# DIGREG1.net
KiCad netlist of a schematic drawn in EAGLE
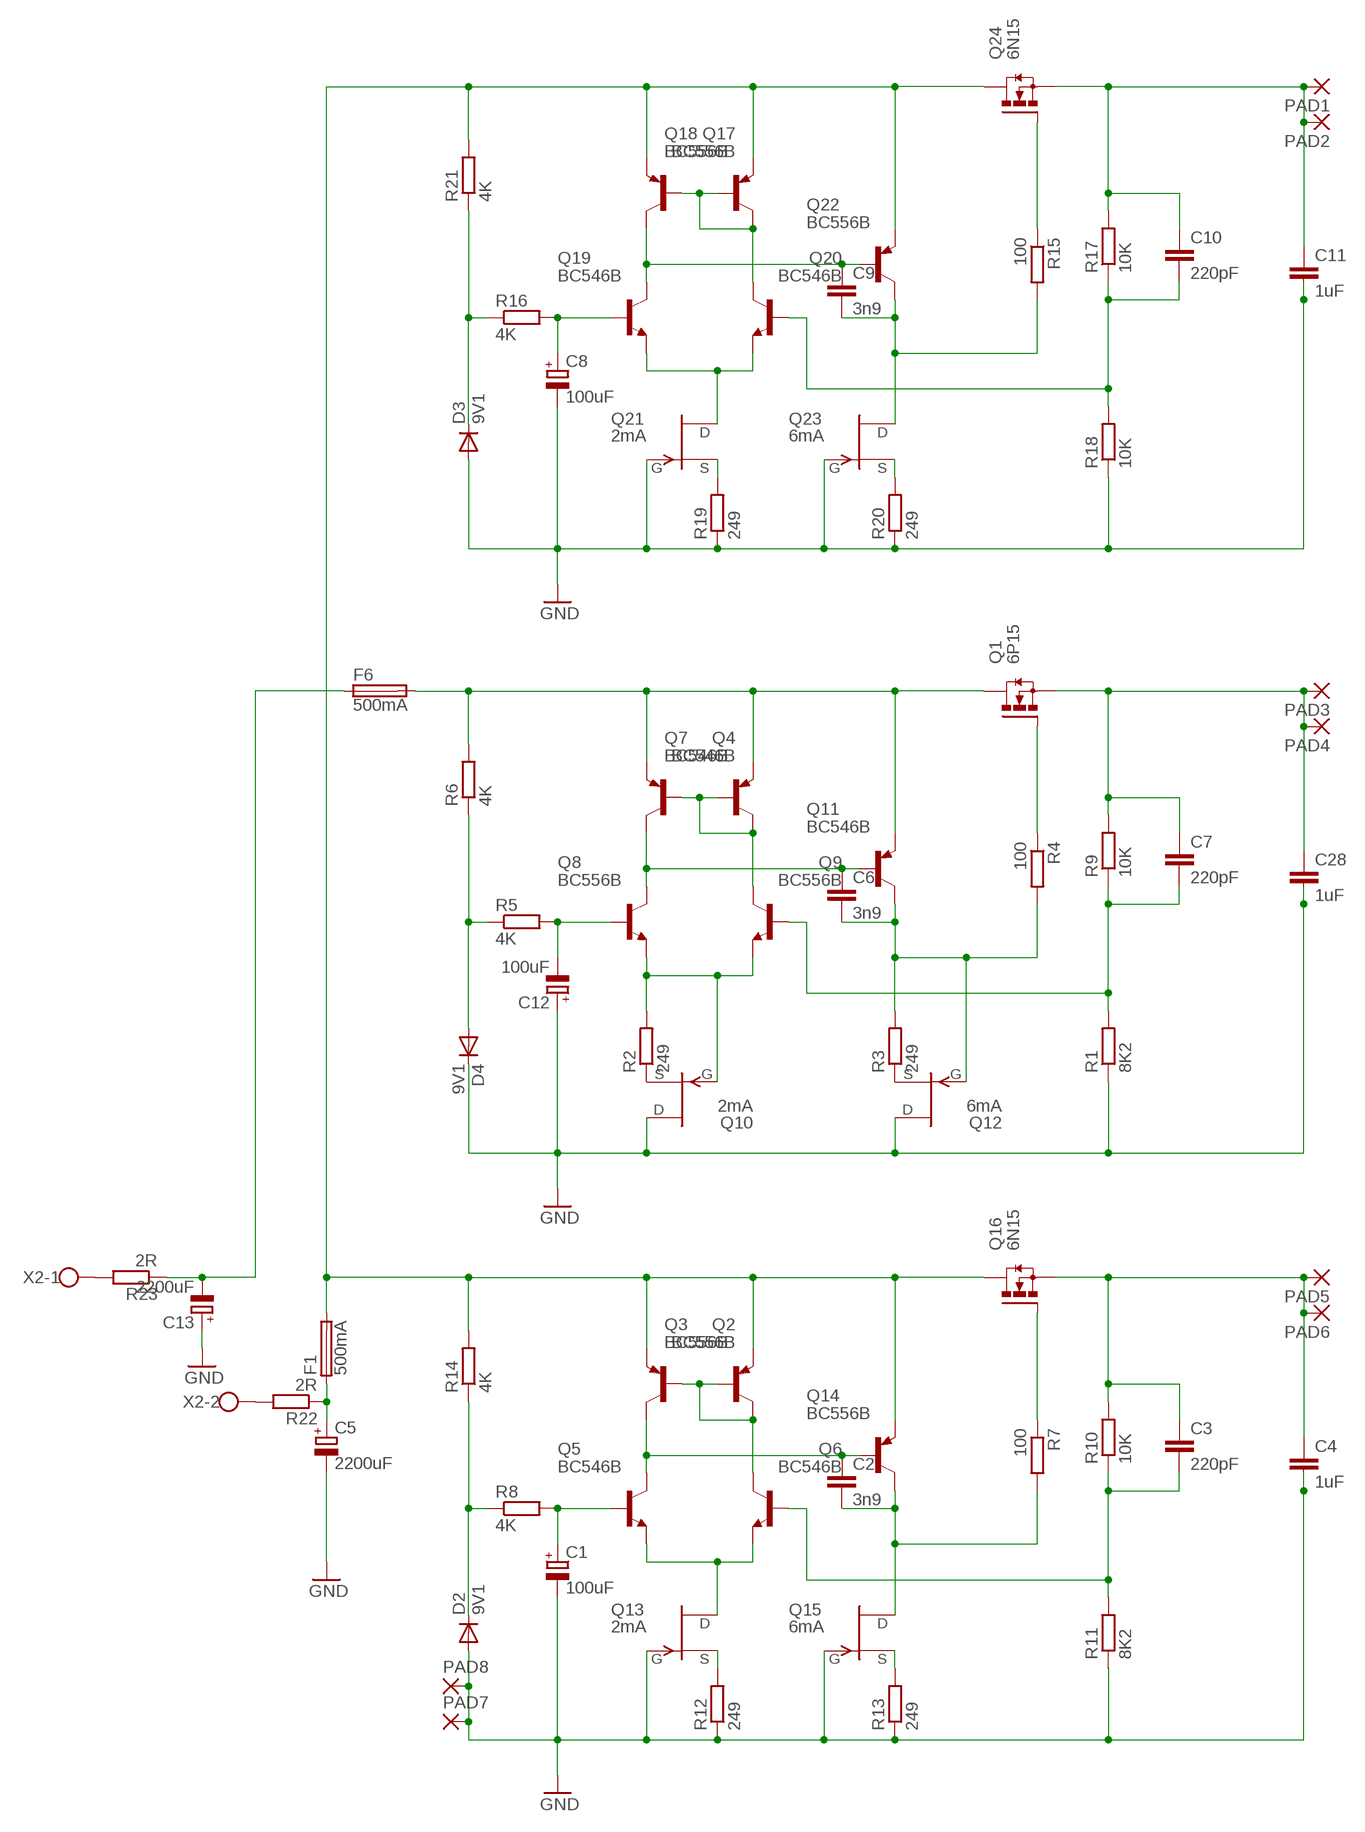
[diagram p0: schematic, sheet 1]

(export (version "E")
  (design (tool "Eeschema 10.0.6"))
  (components
    (comp (ref "C1")
      (value "100uF")
      (footprint "eagle-import:E3,5-8")
      (libsource (lib "eagle-import") (part "CPOL-EUE3.5-8"))
    )
    (comp (ref "C2")
      (value "3n9")
      (footprint "eagle-import:C1210K")
      (libsource (lib "eagle-import") (part "C-EUC1210K"))
    )
    (comp (ref "C3")
      (value "220pF")
      (footprint "eagle-import:C1210")
      (libsource (lib "eagle-import") (part "C-EUC1210"))
    )
    (comp (ref "C4")
      (value "1uF")
      (footprint "eagle-import:C275-134X316")
      (libsource (lib "eagle-import") (part "C-EU275-134X316"))
    )
    (comp (ref "C5")
      (value "2200uF")
      (footprint "eagle-import:E7,5-18")
      (libsource (lib "eagle-import") (part "CPOL-EUE7.5-18"))
    )
    (comp (ref "C6")
      (value "3n9")
      (footprint "eagle-import:C1210K")
      (libsource (lib "eagle-import") (part "C-EUC1210K"))
    )
    (comp (ref "C7")
      (value "220pF")
      (footprint "eagle-import:C1210")
      (libsource (lib "eagle-import") (part "C-EUC1210"))
    )
    (comp (ref "C8")
      (value "100uF")
      (footprint "eagle-import:E3,5-8")
      (libsource (lib "eagle-import") (part "CPOL-EUE3.5-8"))
    )
    (comp (ref "C9")
      (value "3n9")
      (footprint "eagle-import:C1210K")
      (libsource (lib "eagle-import") (part "C-EUC1210K"))
    )
    (comp (ref "C10")
      (value "220pF")
      (footprint "eagle-import:C1210")
      (libsource (lib "eagle-import") (part "C-EUC1210"))
    )
    (comp (ref "C11")
      (value "1uF")
      (footprint "eagle-import:C275-134X316")
      (libsource (lib "eagle-import") (part "C-EU275-134X316"))
    )
    (comp (ref "C12")
      (value "100uF")
      (footprint "eagle-import:E3,5-8")
      (libsource (lib "eagle-import") (part "CPOL-EUE3.5-8"))
    )
    (comp (ref "C13")
      (value "2200uF")
      (footprint "eagle-import:E7,5-18")
      (libsource (lib "eagle-import") (part "CPOL-EUE7.5-18"))
    )
    (comp (ref "C28")
      (value "1uF")
      (footprint "eagle-import:C275-134X316")
      (libsource (lib "eagle-import") (part "C-EU275-134X316"))
    )
    (comp (ref "D2")
      (value "9V1")
      (footprint "eagle-import:DO35-7")
      (libsource (lib "eagle-import") (part "1N4148DO35-7"))
    )
    (comp (ref "D3")
      (value "9V1")
      (footprint "eagle-import:DO35-7")
      (libsource (lib "eagle-import") (part "1N4148DO35-7"))
    )
    (comp (ref "D4")
      (value "9V1")
      (footprint "eagle-import:DO35-7")
      (libsource (lib "eagle-import") (part "1N4148DO35-7"))
    )
    (comp (ref "F1")
      (value "500mA")
      (footprint "eagle-import:19560")
      (libsource (lib "eagle-import") (part "19560"))
    )
    (comp (ref "F6")
      (value "500mA")
      (footprint "eagle-import:19560")
      (libsource (lib "eagle-import") (part "19560"))
    )
    (comp (ref "PAD1")
      (value "3,81/1,4")
      (footprint "eagle-import:3,81_1,4")
      (libsource (lib "eagle-import") (part "3,81/1,4"))
    )
    (comp (ref "PAD2")
      (value "3,81/1,4")
      (footprint "eagle-import:3,81_1,4")
      (libsource (lib "eagle-import") (part "3,81/1,4"))
    )
    (comp (ref "PAD3")
      (value "3,81/1,4")
      (footprint "eagle-import:3,81_1,4")
      (libsource (lib "eagle-import") (part "3,81/1,4"))
    )
    (comp (ref "PAD4")
      (value "3,81/1,4")
      (footprint "eagle-import:3,81_1,4")
      (libsource (lib "eagle-import") (part "3,81/1,4"))
    )
    (comp (ref "PAD5")
      (value "3,81/1,4")
      (footprint "eagle-import:3,81_1,4")
      (libsource (lib "eagle-import") (part "3,81/1,4"))
    )
    (comp (ref "PAD6")
      (value "3,81/1,4")
      (footprint "eagle-import:3,81_1,4")
      (libsource (lib "eagle-import") (part "3,81/1,4"))
    )
    (comp (ref "PAD7")
      (value "3,81/1,4")
      (footprint "eagle-import:3,81_1,4")
      (libsource (lib "eagle-import") (part "3,81/1,4"))
    )
    (comp (ref "PAD8")
      (value "3,81/1,4")
      (footprint "eagle-import:3,81_1,4")
      (libsource (lib "eagle-import") (part "3,81/1,4"))
    )
    (comp (ref "Q1")
      (value "6P15")
      (footprint "eagle-import:TO220BH")
      (libsource (lib "eagle-import") (part "IRFI540NPBF"))
    )
    (comp (ref "Q2")
      (value "BC556B")
      (footprint "eagle-import:TO92-EBC")
      (libsource (lib "eagle-import") (part "BC560"))
    )
    (comp (ref "Q3")
      (value "BC556B")
      (footprint "eagle-import:TO92-EBC")
      (libsource (lib "eagle-import") (part "BC560"))
    )
    (comp (ref "Q4")
      (value "BC546B")
      (footprint "eagle-import:TO92-EBC")
      (libsource (lib "eagle-import") (part "BC560"))
    )
    (comp (ref "Q5")
      (value "BC546B")
      (footprint "eagle-import:TO92-EBC")
      (libsource (lib "eagle-import") (part "BC550B"))
    )
    (comp (ref "Q6")
      (value "BC546B")
      (footprint "eagle-import:TO92-EBC")
      (libsource (lib "eagle-import") (part "BC550B"))
    )
    (comp (ref "Q7")
      (value "BC546B")
      (footprint "eagle-import:TO92-EBC")
      (libsource (lib "eagle-import") (part "BC560"))
    )
    (comp (ref "Q8")
      (value "BC556B")
      (footprint "eagle-import:TO92-EBC")
      (libsource (lib "eagle-import") (part "BC550B"))
    )
    (comp (ref "Q9")
      (value "BC556B")
      (footprint "eagle-import:TO92-EBC")
      (libsource (lib "eagle-import") (part "BC550B"))
    )
    (comp (ref "Q10")
      (value "2mA")
      (footprint "eagle-import:TO92-")
      (libsource (lib "eagle-import") (part "?5482N4"))
    )
    (comp (ref "Q11")
      (value "BC546B")
      (footprint "eagle-import:TO92-EBC")
      (libsource (lib "eagle-import") (part "BC560"))
    )
    (comp (ref "Q12")
      (value "6mA")
      (footprint "eagle-import:TO92-")
      (libsource (lib "eagle-import") (part "?5482N4"))
    )
    (comp (ref "Q13")
      (value "2mA")
      (footprint "eagle-import:TO92-")
      (libsource (lib "eagle-import") (part "?5482N4"))
    )
    (comp (ref "Q14")
      (value "BC556B")
      (footprint "eagle-import:TO92-EBC")
      (libsource (lib "eagle-import") (part "BC560"))
    )
    (comp (ref "Q15")
      (value "6mA")
      (footprint "eagle-import:TO92-")
      (libsource (lib "eagle-import") (part "?5482N4"))
    )
    (comp (ref "Q16")
      (value "6N15")
      (footprint "eagle-import:TO220BH")
      (libsource (lib "eagle-import") (part "IRFI540NPBF"))
    )
    (comp (ref "Q17")
      (value "BC556B")
      (footprint "eagle-import:TO92-EBC")
      (libsource (lib "eagle-import") (part "BC560"))
    )
    (comp (ref "Q18")
      (value "BC556B")
      (footprint "eagle-import:TO92-EBC")
      (libsource (lib "eagle-import") (part "BC560"))
    )
    (comp (ref "Q19")
      (value "BC546B")
      (footprint "eagle-import:TO92-EBC")
      (libsource (lib "eagle-import") (part "BC550B"))
    )
    (comp (ref "Q20")
      (value "BC546B")
      (footprint "eagle-import:TO92-EBC")
      (libsource (lib "eagle-import") (part "BC550B"))
    )
    (comp (ref "Q21")
      (value "2mA")
      (footprint "eagle-import:TO92-")
      (libsource (lib "eagle-import") (part "?5482N4"))
    )
    (comp (ref "Q22")
      (value "BC556B")
      (footprint "eagle-import:TO92-EBC")
      (libsource (lib "eagle-import") (part "BC560"))
    )
    (comp (ref "Q23")
      (value "6mA")
      (footprint "eagle-import:TO92-")
      (libsource (lib "eagle-import") (part "?5482N4"))
    )
    (comp (ref "Q24")
      (value "6N15")
      (footprint "eagle-import:TO220BH")
      (libsource (lib "eagle-import") (part "IRFI540NPBF"))
    )
    (comp (ref "R1")
      (value "8K2")
      (footprint "eagle-import:R1210")
      (libsource (lib "eagle-import") (part "R-EU_R1210"))
    )
    (comp (ref "R2")
      (value "249")
      (footprint "eagle-import:R1210")
      (libsource (lib "eagle-import") (part "R-EU_R1210"))
    )
    (comp (ref "R3")
      (value "249")
      (footprint "eagle-import:R1210")
      (libsource (lib "eagle-import") (part "R-EU_R1210"))
    )
    (comp (ref "R4")
      (value "100")
      (footprint "eagle-import:0309_12")
      (libsource (lib "eagle-import") (part "R-EU_0309/12"))
    )
    (comp (ref "R5")
      (value "4K")
      (footprint "eagle-import:0309_12")
      (libsource (lib "eagle-import") (part "R-EU_0309/12"))
    )
    (comp (ref "R6")
      (value "4K")
      (footprint "eagle-import:0309_12")
      (libsource (lib "eagle-import") (part "R-EU_0309/12"))
    )
    (comp (ref "R7")
      (value "100")
      (footprint "eagle-import:0309_12")
      (libsource (lib "eagle-import") (part "R-EU_0309/12"))
    )
    (comp (ref "R8")
      (value "4K")
      (footprint "eagle-import:0309_12")
      (libsource (lib "eagle-import") (part "R-EU_0309/12"))
    )
    (comp (ref "R9")
      (value "10K")
      (footprint "eagle-import:R1210")
      (libsource (lib "eagle-import") (part "R-EU_R1210"))
    )
    (comp (ref "R10")
      (value "10K")
      (footprint "eagle-import:R1210")
      (libsource (lib "eagle-import") (part "R-EU_R1210"))
    )
    (comp (ref "R11")
      (value "8K2")
      (footprint "eagle-import:R1210")
      (libsource (lib "eagle-import") (part "R-EU_R1210"))
    )
    (comp (ref "R12")
      (value "249")
      (footprint "eagle-import:R1210")
      (libsource (lib "eagle-import") (part "R-EU_R1210"))
    )
    (comp (ref "R13")
      (value "249")
      (footprint "eagle-import:R1210")
      (libsource (lib "eagle-import") (part "R-EU_R1210"))
    )
    (comp (ref "R14")
      (value "4K")
      (footprint "eagle-import:0309_12")
      (libsource (lib "eagle-import") (part "R-EU_0309/12"))
    )
    (comp (ref "R15")
      (value "100")
      (footprint "eagle-import:0309_12")
      (libsource (lib "eagle-import") (part "R-EU_0309/12"))
    )
    (comp (ref "R16")
      (value "4K")
      (footprint "eagle-import:0309_12")
      (libsource (lib "eagle-import") (part "R-EU_0309/12"))
    )
    (comp (ref "R17")
      (value "10K")
      (footprint "eagle-import:R1210")
      (libsource (lib "eagle-import") (part "R-EU_R1210"))
    )
    (comp (ref "R18")
      (value "10K")
      (footprint "eagle-import:R1210")
      (libsource (lib "eagle-import") (part "R-EU_R1210"))
    )
    (comp (ref "R19")
      (value "249")
      (footprint "eagle-import:R1210")
      (libsource (lib "eagle-import") (part "R-EU_R1210"))
    )
    (comp (ref "R20")
      (value "249")
      (footprint "eagle-import:R1210")
      (libsource (lib "eagle-import") (part "R-EU_R1210"))
    )
    (comp (ref "R21")
      (value "4K")
      (footprint "eagle-import:0309_12")
      (libsource (lib "eagle-import") (part "R-EU_0309/12"))
    )
    (comp (ref "R22")
      (value "2R")
      (footprint "eagle-import:0309_12")
      (libsource (lib "eagle-import") (part "R-EU_0309/12"))
    )
    (comp (ref "R23")
      (value "2R")
      (footprint "eagle-import:0309_12")
      (libsource (lib "eagle-import") (part "R-EU_0309/12"))
    )
    (comp (ref "X2")
      (value "W237-102")
      (footprint "eagle-import:W237-102")
      (fields
        (field (name "MPN") "237-102")
        (field (name "MPN_1") "237-102")
        (field (name "OC_FARNELL") "unknown")
        (field (name "OC_NEWARK") "70K9898")
      )
      (libsource (lib "eagle-import") (part "W237-102"))
    )
  )
  (nets
    (net (code "1") (name "GND") (class "Default")
      (node (ref "C1") (pin "-") (pinfunction "-_-") (pintype "passive"))
      (node (ref "C11") (pin "2") (pinfunction "2_2") (pintype "passive"))
      (node (ref "C12") (pin "+") (pinfunction "+_+") (pintype "passive"))
      (node (ref "C13") (pin "+") (pinfunction "+_+") (pintype "passive"))
      (node (ref "C28") (pin "2") (pinfunction "2_2") (pintype "passive"))
      (node (ref "C4") (pin "2") (pinfunction "2_2") (pintype "passive"))
      (node (ref "C5") (pin "-") (pinfunction "-_-") (pintype "passive"))
      (node (ref "C8") (pin "-") (pinfunction "-_-") (pintype "passive"))
      (node (ref "D2") (pin "A") (pinfunction "A_A") (pintype "passive"))
      (node (ref "D3") (pin "A") (pinfunction "A_A") (pintype "passive"))
      (node (ref "D4") (pin "C") (pinfunction "C_C") (pintype "passive"))
      (node (ref "PAD7") (pin "1") (pinfunction "P_1") (pintype "passive"))
      (node (ref "PAD8") (pin "1") (pinfunction "P_1") (pintype "passive"))
      (node (ref "Q10") (pin "3") (pinfunction "D_3") (pintype "passive"))
      (node (ref "Q12") (pin "3") (pinfunction "D_3") (pintype "passive"))
      (node (ref "Q13") (pin "1") (pinfunction "G_1") (pintype "passive"))
      (node (ref "Q15") (pin "1") (pinfunction "G_1") (pintype "passive"))
      (node (ref "Q21") (pin "1") (pinfunction "G_1") (pintype "passive"))
      (node (ref "Q23") (pin "1") (pinfunction "G_1") (pintype "passive"))
      (node (ref "R1") (pin "1") (pinfunction "1_1") (pintype "passive"))
      (node (ref "R11") (pin "1") (pinfunction "1_1") (pintype "passive"))
      (node (ref "R12") (pin "1") (pinfunction "1_1") (pintype "passive"))
      (node (ref "R13") (pin "1") (pinfunction "1_1") (pintype "passive"))
      (node (ref "R18") (pin "1") (pinfunction "1_1") (pintype "passive"))
      (node (ref "R19") (pin "1") (pinfunction "1_1") (pintype "passive"))
      (node (ref "R20") (pin "1") (pinfunction "1_1") (pintype "passive"))
    )
    (net (code "2") (name "Net-(C1-Pad+)") (class "Default")
      (node (ref "C1") (pin "+") (pinfunction "+_+") (pintype "passive"))
      (node (ref "Q5") (pin "B") (pinfunction "B_B") (pintype "passive"))
      (node (ref "R8") (pin "2") (pinfunction "2_2") (pintype "passive"))
    )
    (net (code "3") (name "Net-(C2-Pad1)") (class "Default")
      (node (ref "C2") (pin "1") (pinfunction "1_1") (pintype "passive"))
      (node (ref "Q14") (pin "B") (pinfunction "B_B") (pintype "passive"))
      (node (ref "Q2") (pin "C") (pinfunction "C_C") (pintype "passive"))
      (node (ref "Q5") (pin "C") (pinfunction "C_C") (pintype "passive"))
    )
    (net (code "4") (name "Net-(C3-Pad2)") (class "Default")
      (node (ref "C3") (pin "2") (pinfunction "2_2") (pintype "passive"))
      (node (ref "Q6") (pin "B") (pinfunction "B_B") (pintype "passive"))
      (node (ref "R10") (pin "1") (pinfunction "1_1") (pintype "passive"))
      (node (ref "R11") (pin "2") (pinfunction "2_2") (pintype "passive"))
    )
    (net (code "5") (name "Net-(C5-Pad+)") (class "Default")
      (node (ref "C5") (pin "+") (pinfunction "+_+") (pintype "passive"))
      (node (ref "F1") (pin "1") (pinfunction "1_1") (pintype "passive"))
      (node (ref "R22") (pin "1") (pinfunction "1_1") (pintype "passive"))
    )
    (net (code "6") (name "Net-(C6-Pad1)") (class "Default")
      (node (ref "C6") (pin "1") (pinfunction "1_1") (pintype "passive"))
      (node (ref "Q11") (pin "B") (pinfunction "B_B") (pintype "passive"))
      (node (ref "Q4") (pin "C") (pinfunction "C_C") (pintype "passive"))
      (node (ref "Q8") (pin "C") (pinfunction "C_C") (pintype "passive"))
    )
    (net (code "7") (name "Net-(C7-Pad2)") (class "Default")
      (node (ref "C7") (pin "2") (pinfunction "2_2") (pintype "passive"))
      (node (ref "Q9") (pin "B") (pinfunction "B_B") (pintype "passive"))
      (node (ref "R1") (pin "2") (pinfunction "2_2") (pintype "passive"))
      (node (ref "R9") (pin "1") (pinfunction "1_1") (pintype "passive"))
    )
    (net (code "8") (name "Net-(C8-Pad+)") (class "Default")
      (node (ref "C8") (pin "+") (pinfunction "+_+") (pintype "passive"))
      (node (ref "Q19") (pin "B") (pinfunction "B_B") (pintype "passive"))
      (node (ref "R16") (pin "2") (pinfunction "2_2") (pintype "passive"))
    )
    (net (code "9") (name "Net-(C9-Pad1)") (class "Default")
      (node (ref "C9") (pin "1") (pinfunction "1_1") (pintype "passive"))
      (node (ref "Q17") (pin "C") (pinfunction "C_C") (pintype "passive"))
      (node (ref "Q19") (pin "C") (pinfunction "C_C") (pintype "passive"))
      (node (ref "Q22") (pin "B") (pinfunction "B_B") (pintype "passive"))
    )
    (net (code "10") (name "Net-(C10-Pad2)") (class "Default")
      (node (ref "C10") (pin "2") (pinfunction "2_2") (pintype "passive"))
      (node (ref "Q20") (pin "B") (pinfunction "B_B") (pintype "passive"))
      (node (ref "R17") (pin "1") (pinfunction "1_1") (pintype "passive"))
      (node (ref "R18") (pin "2") (pinfunction "2_2") (pintype "passive"))
    )
    (net (code "11") (name "Net-(C12-Pad-)") (class "Default")
      (node (ref "C12") (pin "-") (pinfunction "-_-") (pintype "passive"))
      (node (ref "Q8") (pin "B") (pinfunction "B_B") (pintype "passive"))
      (node (ref "R5") (pin "2") (pinfunction "2_2") (pintype "passive"))
    )
    (net (code "12") (name "Net-(C13-Pad-)") (class "Default")
      (node (ref "C13") (pin "-") (pinfunction "-_-") (pintype "passive"))
      (node (ref "F6") (pin "1") (pinfunction "1_1") (pintype "passive"))
      (node (ref "R23") (pin "1") (pinfunction "1_1") (pintype "passive"))
    )
    (net (code "13") (name "Net-(D2-PadC)") (class "Default")
      (node (ref "D2") (pin "C") (pinfunction "C_C") (pintype "passive"))
      (node (ref "R14") (pin "1") (pinfunction "1_1") (pintype "passive"))
      (node (ref "R8") (pin "1") (pinfunction "1_1") (pintype "passive"))
    )
    (net (code "14") (name "Net-(D3-PadC)") (class "Default")
      (node (ref "D3") (pin "C") (pinfunction "C_C") (pintype "passive"))
      (node (ref "R16") (pin "1") (pinfunction "1_1") (pintype "passive"))
      (node (ref "R21") (pin "1") (pinfunction "1_1") (pintype "passive"))
    )
    (net (code "15") (name "Net-(D4-PadA)") (class "Default")
      (node (ref "D4") (pin "A") (pinfunction "A_A") (pintype "passive"))
      (node (ref "R5") (pin "1") (pinfunction "1_1") (pintype "passive"))
      (node (ref "R6") (pin "1") (pinfunction "1_1") (pintype "passive"))
    )
    (net (code "16") (name "Net-(F1-Pad2)") (class "Default")
      (node (ref "F1") (pin "2") (pinfunction "2_2") (pintype "passive"))
      (node (ref "Q14") (pin "E") (pinfunction "E_E") (pintype "passive"))
      (node (ref "Q16") (pin "D") (pinfunction "D_D") (pintype "passive"))
      (node (ref "Q17") (pin "E") (pinfunction "E_E") (pintype "passive"))
      (node (ref "Q18") (pin "E") (pinfunction "E_E") (pintype "passive"))
      (node (ref "Q2") (pin "E") (pinfunction "E_E") (pintype "passive"))
      (node (ref "Q22") (pin "E") (pinfunction "E_E") (pintype "passive"))
      (node (ref "Q24") (pin "D") (pinfunction "D_D") (pintype "passive"))
      (node (ref "Q3") (pin "E") (pinfunction "E_E") (pintype "passive"))
      (node (ref "R14") (pin "2") (pinfunction "2_2") (pintype "passive"))
      (node (ref "R21") (pin "2") (pinfunction "2_2") (pintype "passive"))
    )
    (net (code "17") (name "Net-(F6-Pad2)") (class "Default")
      (node (ref "F6") (pin "2") (pinfunction "2_2") (pintype "passive"))
      (node (ref "Q1") (pin "D") (pinfunction "D_D") (pintype "passive"))
      (node (ref "Q11") (pin "E") (pinfunction "E_E") (pintype "passive"))
      (node (ref "Q4") (pin "E") (pinfunction "E_E") (pintype "passive"))
      (node (ref "Q7") (pin "E") (pinfunction "E_E") (pintype "passive"))
      (node (ref "R6") (pin "2") (pinfunction "2_2") (pintype "passive"))
    )
    (net (code "18") (name "Net-(PAD1-P)") (class "Default")
      (node (ref "C10") (pin "1") (pinfunction "1_1") (pintype "passive"))
      (node (ref "C11") (pin "1") (pinfunction "1_1") (pintype "passive"))
      (node (ref "PAD1") (pin "1") (pinfunction "P_1") (pintype "passive"))
      (node (ref "PAD2") (pin "1") (pinfunction "P_1") (pintype "passive"))
      (node (ref "Q24") (pin "S") (pinfunction "S_S") (pintype "passive"))
      (node (ref "R17") (pin "2") (pinfunction "2_2") (pintype "passive"))
    )
    (net (code "19") (name "Net-(PAD3-P)") (class "Default")
      (node (ref "C28") (pin "1") (pinfunction "1_1") (pintype "passive"))
      (node (ref "C7") (pin "1") (pinfunction "1_1") (pintype "passive"))
      (node (ref "PAD3") (pin "1") (pinfunction "P_1") (pintype "passive"))
      (node (ref "PAD4") (pin "1") (pinfunction "P_1") (pintype "passive"))
      (node (ref "Q1") (pin "S") (pinfunction "S_S") (pintype "passive"))
      (node (ref "R9") (pin "2") (pinfunction "2_2") (pintype "passive"))
    )
    (net (code "20") (name "Net-(PAD5-P)") (class "Default")
      (node (ref "C3") (pin "1") (pinfunction "1_1") (pintype "passive"))
      (node (ref "C4") (pin "1") (pinfunction "1_1") (pintype "passive"))
      (node (ref "PAD5") (pin "1") (pinfunction "P_1") (pintype "passive"))
      (node (ref "PAD6") (pin "1") (pinfunction "P_1") (pintype "passive"))
      (node (ref "Q16") (pin "S") (pinfunction "S_S") (pintype "passive"))
      (node (ref "R10") (pin "2") (pinfunction "2_2") (pintype "passive"))
    )
    (net (code "21") (name "Net-(Q1-PadG)") (class "Default")
      (node (ref "Q1") (pin "G") (pinfunction "G_G") (pintype "passive"))
      (node (ref "R4") (pin "1") (pinfunction "1_1") (pintype "passive"))
    )
    (net (code "22") (name "Net-(Q2-PadB)") (class "Default")
      (node (ref "Q2") (pin "B") (pinfunction "B_B") (pintype "passive"))
      (node (ref "Q3") (pin "B") (pinfunction "B_B") (pintype "passive"))
      (node (ref "Q3") (pin "C") (pinfunction "C_C") (pintype "passive"))
      (node (ref "Q6") (pin "C") (pinfunction "C_C") (pintype "passive"))
    )
    (net (code "23") (name "Net-(Q4-PadB)") (class "Default")
      (node (ref "Q4") (pin "B") (pinfunction "B_B") (pintype "passive"))
      (node (ref "Q7") (pin "B") (pinfunction "B_B") (pintype "passive"))
      (node (ref "Q7") (pin "C") (pinfunction "C_C") (pintype "passive"))
      (node (ref "Q9") (pin "C") (pinfunction "C_C") (pintype "passive"))
    )
    (net (code "24") (name "Net-(Q10-G)") (class "Default")
      (node (ref "Q10") (pin "1") (pinfunction "G_1") (pintype "passive"))
      (node (ref "Q8") (pin "E") (pinfunction "E_E") (pintype "passive"))
      (node (ref "Q9") (pin "E") (pinfunction "E_E") (pintype "passive"))
      (node (ref "R2") (pin "2") (pinfunction "2_2") (pintype "passive"))
    )
    (net (code "25") (name "Net-(Q10-S)") (class "Default")
      (node (ref "Q10") (pin "2") (pinfunction "S_2") (pintype "passive"))
      (node (ref "R2") (pin "1") (pinfunction "1_1") (pintype "passive"))
    )
    (net (code "26") (name "Net-(Q12-G)") (class "Default")
      (node (ref "C6") (pin "2") (pinfunction "2_2") (pintype "passive"))
      (node (ref "Q11") (pin "C") (pinfunction "C_C") (pintype "passive"))
      (node (ref "Q12") (pin "1") (pinfunction "G_1") (pintype "passive"))
      (node (ref "R3") (pin "2") (pinfunction "2_2") (pintype "passive"))
      (node (ref "R4") (pin "2") (pinfunction "2_2") (pintype "passive"))
    )
    (net (code "27") (name "Net-(Q12-S)") (class "Default")
      (node (ref "Q12") (pin "2") (pinfunction "S_2") (pintype "passive"))
      (node (ref "R3") (pin "1") (pinfunction "1_1") (pintype "passive"))
    )
    (net (code "28") (name "Net-(Q13-D)") (class "Default")
      (node (ref "Q13") (pin "3") (pinfunction "D_3") (pintype "passive"))
      (node (ref "Q5") (pin "E") (pinfunction "E_E") (pintype "passive"))
      (node (ref "Q6") (pin "E") (pinfunction "E_E") (pintype "passive"))
    )
    (net (code "29") (name "Net-(Q13-S)") (class "Default")
      (node (ref "Q13") (pin "2") (pinfunction "S_2") (pintype "passive"))
      (node (ref "R12") (pin "2") (pinfunction "2_2") (pintype "passive"))
    )
    (net (code "30") (name "Net-(Q15-D)") (class "Default")
      (node (ref "C2") (pin "2") (pinfunction "2_2") (pintype "passive"))
      (node (ref "Q14") (pin "C") (pinfunction "C_C") (pintype "passive"))
      (node (ref "Q15") (pin "3") (pinfunction "D_3") (pintype "passive"))
      (node (ref "R7") (pin "2") (pinfunction "2_2") (pintype "passive"))
    )
    (net (code "31") (name "Net-(Q15-S)") (class "Default")
      (node (ref "Q15") (pin "2") (pinfunction "S_2") (pintype "passive"))
      (node (ref "R13") (pin "2") (pinfunction "2_2") (pintype "passive"))
    )
    (net (code "32") (name "Net-(Q16-PadG)") (class "Default")
      (node (ref "Q16") (pin "G") (pinfunction "G_G") (pintype "passive"))
      (node (ref "R7") (pin "1") (pinfunction "1_1") (pintype "passive"))
    )
    (net (code "33") (name "Net-(Q17-PadB)") (class "Default")
      (node (ref "Q17") (pin "B") (pinfunction "B_B") (pintype "passive"))
      (node (ref "Q18") (pin "B") (pinfunction "B_B") (pintype "passive"))
      (node (ref "Q18") (pin "C") (pinfunction "C_C") (pintype "passive"))
      (node (ref "Q20") (pin "C") (pinfunction "C_C") (pintype "passive"))
    )
    (net (code "34") (name "Net-(Q21-D)") (class "Default")
      (node (ref "Q19") (pin "E") (pinfunction "E_E") (pintype "passive"))
      (node (ref "Q20") (pin "E") (pinfunction "E_E") (pintype "passive"))
      (node (ref "Q21") (pin "3") (pinfunction "D_3") (pintype "passive"))
    )
    (net (code "35") (name "Net-(Q21-S)") (class "Default")
      (node (ref "Q21") (pin "2") (pinfunction "S_2") (pintype "passive"))
      (node (ref "R19") (pin "2") (pinfunction "2_2") (pintype "passive"))
    )
    (net (code "36") (name "Net-(Q23-D)") (class "Default")
      (node (ref "C9") (pin "2") (pinfunction "2_2") (pintype "passive"))
      (node (ref "Q22") (pin "C") (pinfunction "C_C") (pintype "passive"))
      (node (ref "Q23") (pin "3") (pinfunction "D_3") (pintype "passive"))
      (node (ref "R15") (pin "2") (pinfunction "2_2") (pintype "passive"))
    )
    (net (code "37") (name "Net-(Q23-S)") (class "Default")
      (node (ref "Q23") (pin "2") (pinfunction "S_2") (pintype "passive"))
      (node (ref "R20") (pin "2") (pinfunction "2_2") (pintype "passive"))
    )
    (net (code "38") (name "Net-(Q24-PadG)") (class "Default")
      (node (ref "Q24") (pin "G") (pinfunction "G_G") (pintype "passive"))
      (node (ref "R15") (pin "1") (pinfunction "1_1") (pintype "passive"))
    )
    (net (code "39") (name "Net-(X2A-KL)") (class "Default")
      (node (ref "R23") (pin "2") (pinfunction "2_2") (pintype "passive"))
      (node (ref "X2") (pin "1") (pinfunction "KL_1") (pintype "passive"))
    )
    (net (code "40") (name "Net-(X2B-KL)") (class "Default")
      (node (ref "R22") (pin "2") (pinfunction "2_2") (pintype "passive"))
      (node (ref "X2") (pin "2") (pinfunction "KL_2") (pintype "passive"))
    )
  )
)
